# power_supply1.net
KiCad netlist of a schematic drawn in EAGLE
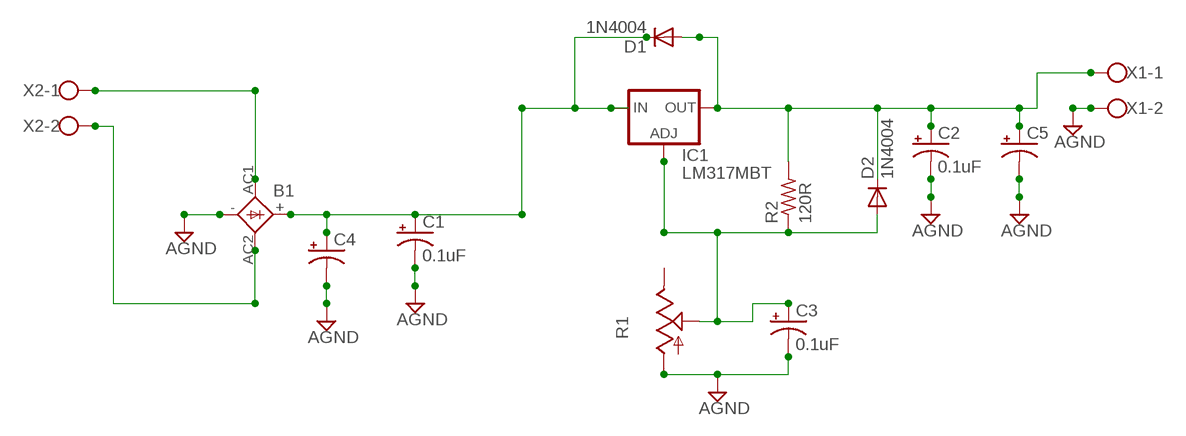
[diagram p0: schematic, sheet 1]

(export (version "E")
  (design (tool "Eeschema 10.0.6"))
  (components
    (comp (ref "B1")
      (value "GBPC1")
      (footprint "eagle-import:GBPC1")
      (libsource (lib "eagle-import") (part "GBPC1"))
    )
    (comp (ref "C1")
      (value "0.1uF")
      (footprint "eagle-import:TAP5-45")
      (libsource (lib "eagle-import") (part "CPOL-USTAP5-45"))
    )
    (comp (ref "C2")
      (value "0.1uF")
      (footprint "eagle-import:TAP5-45")
      (libsource (lib "eagle-import") (part "CPOL-USTAP5-45"))
    )
    (comp (ref "C3")
      (value "0.1uF")
      (footprint "eagle-import:TAP5-45")
      (libsource (lib "eagle-import") (part "CPOL-USTAP5-45"))
    )
    (comp (ref "C4")
      (value "CPOL-USE7.5-16")
      (footprint "eagle-import:E7,5-16")
      (libsource (lib "eagle-import") (part "CPOL-USE7.5-16"))
    )
    (comp (ref "C5")
      (value "CPOL-USE5-8.5")
      (footprint "eagle-import:E5-8,5")
      (libsource (lib "eagle-import") (part "CPOL-USE5-8.5"))
    )
    (comp (ref "D1")
      (value "1N4004")
      (footprint "eagle-import:DO41-10")
      (libsource (lib "eagle-import") (part "1N4004"))
    )
    (comp (ref "D2")
      (value "1N4004")
      (footprint "eagle-import:DO41-10")
      (libsource (lib "eagle-import") (part "1N4004"))
    )
    (comp (ref "IC1")
      (value "LM317MBT")
      (footprint "eagle-import:TO220L1")
      (libsource (lib "eagle-import") (part "LM317?MBT"))
    )
    (comp (ref "R1")
      (value "TRIM_US-CA9V")
      (footprint "eagle-import:CA9V")
      (libsource (lib "eagle-import") (part "TRIM_US-CA9V"))
    )
    (comp (ref "R2")
      (value "120R")
      (footprint "eagle-import:0207_10")
      (libsource (lib "eagle-import") (part "R-US_0207/10"))
    )
    (comp (ref "X1")
      (value "W237-102")
      (footprint "eagle-import:W237-102")
      (fields (field (name "MPN") "237-102"))
      (libsource (lib "eagle-import") (part "W237-102"))
    )
    (comp (ref "X2")
      (value "W237-102")
      (footprint "eagle-import:W237-102")
      (fields (field (name "MPN") "237-102"))
      (libsource (lib "eagle-import") (part "W237-102"))
    )
  )
  (nets
    (net (code "1") (name "AGND") (class "Default")
      (node (ref "B1") (pin "-") (pinfunction "-_-") (pintype "passive"))
      (node (ref "C1") (pin "-") (pinfunction "-_-") (pintype "passive"))
      (node (ref "C2") (pin "-") (pinfunction "-_-") (pintype "passive"))
      (node (ref "C3") (pin "-") (pinfunction "-_-") (pintype "passive"))
      (node (ref "C4") (pin "-") (pinfunction "-_-") (pintype "passive"))
      (node (ref "C5") (pin "-") (pinfunction "-_-") (pintype "passive"))
      (node (ref "R1") (pin "A") (pinfunction "A_A") (pintype "passive"))
      (node (ref "X1") (pin "2") (pinfunction "KL_2") (pintype "passive"))
    )
    (net (code "2") (name "Net-(IC1-ADJ)") (class "Default")
      (node (ref "C3") (pin "+") (pinfunction "+_+") (pintype "passive"))
      (node (ref "D2") (pin "A") (pinfunction "A_A") (pintype "passive"))
      (node (ref "IC1") (pin "1") (pinfunction "ADJ_1") (pintype "input"))
      (node (ref "R1") (pin "S") (pinfunction "S_S") (pintype "passive"))
      (node (ref "R2") (pin "1") (pinfunction "1_1") (pintype "passive"))
    )
    (net (code "3") (name "Net-(IC1-IN)") (class "Default")
      (node (ref "B1") (pin "+") (pinfunction "+_+") (pintype "passive"))
      (node (ref "C1") (pin "+") (pinfunction "+_+") (pintype "passive"))
      (node (ref "C4") (pin "+") (pinfunction "+_+") (pintype "passive"))
      (node (ref "D1") (pin "C") (pinfunction "C_C") (pintype "passive"))
      (node (ref "IC1") (pin "3") (pinfunction "IN_3") (pintype "input"))
    )
    (net (code "4") (name "Net-(IC1-OUT)") (class "Default")
      (node (ref "C2") (pin "+") (pinfunction "+_+") (pintype "passive"))
      (node (ref "C5") (pin "+") (pinfunction "+_+") (pintype "passive"))
      (node (ref "D1") (pin "A") (pinfunction "A_A") (pintype "passive"))
      (node (ref "D2") (pin "C") (pinfunction "C_C") (pintype "passive"))
      (node (ref "IC1") (pin "2") (pinfunction "OUT_2") (pintype "passive"))
      (node (ref "R2") (pin "2") (pinfunction "2_2") (pintype "passive"))
      (node (ref "X1") (pin "1") (pinfunction "KL_1") (pintype "passive"))
    )
    (net (code "5") (name "Net-(X2A-KL)") (class "Default")
      (node (ref "B1") (pin "AC1") (pinfunction "AC1_AC1") (pintype "passive"))
      (node (ref "X2") (pin "1") (pinfunction "KL_1") (pintype "passive"))
    )
    (net (code "6") (name "Net-(X2B-KL)") (class "Default")
      (node (ref "B1") (pin "AC2") (pinfunction "AC2_AC2") (pintype "passive"))
      (node (ref "X2") (pin "2") (pinfunction "KL_2") (pintype "passive"))
    )
    (net (code "7") (name "unconnected-(R1-PadE)") (class "Default")
      (node (ref "R1") (pin "E") (pinfunction "E_E") (pintype "passive"))
    )
  )
)
